# adapter.net
KiCad netlist of a schematic drawn in EAGLE
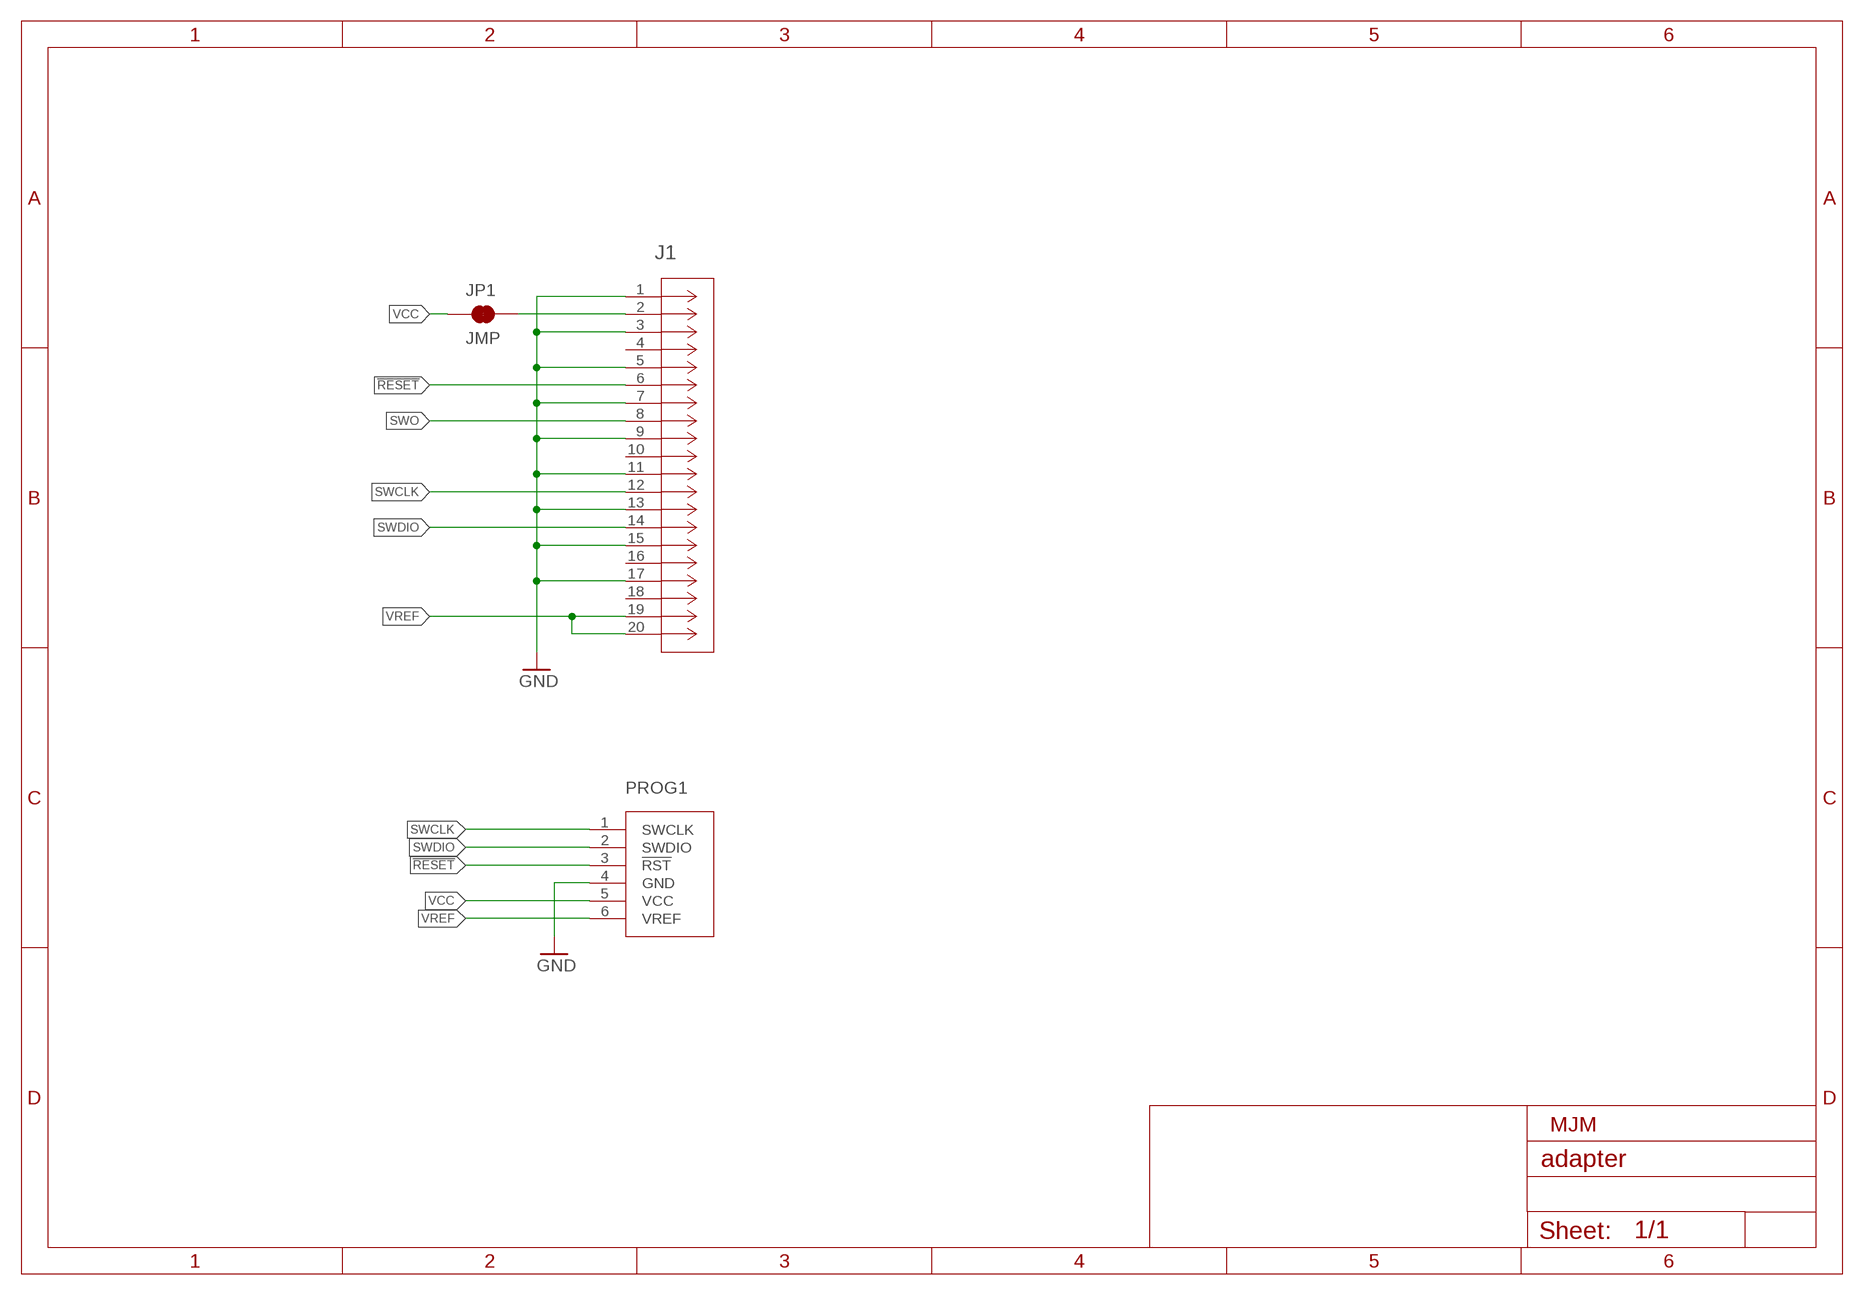
[diagram p0: schematic, sheet 1]

(export (version "E")
  (design (tool "Eeschema 10.0.6"))
  (components
    (comp (ref "J1")
      (value "SFH11-PBPC-D10-ST-BK")
      (footprint "eagle-import:CONN_SFH11-PBPC-D10-ST-BK_SUL")
      (fields (field (name "COPYRIGHT") "Copyright (C) 2018 Accelerated Designs. All rights reserved"))
      (libsource (lib "eagle-import") (part "SFH11-PBPC-D10-ST-BK"))
    )
    (comp (ref "JP1")
      (value "JMP")
      (footprint "eagle-import:SMT-JUMPER_2_NC_TRACE_SILK")
      (libsource (lib "eagle-import") (part "JUMPER-SMT_2_NC_TRACE_SILK"))
    )
    (comp (ref "PROG1")
      (value "0532610671_OP")
      (footprint "eagle-import:0532610671")
      (libsource (lib "eagle-import") (part "0532610671_OP"))
    )
  )
  (nets
    (net (code "1") (name "/~{RESET}") (class "Default")
      (node (ref "J1") (pin "6") (pinfunction "6_6") (pintype "passive"))
      (node (ref "PROG1") (pin "3") (pinfunction "~{RST}_3") (pintype "bidirectional"))
    )
    (net (code "2") (name "GND") (class "Default")
      (node (ref "J1") (pin "1") (pinfunction "1_1") (pintype "passive"))
      (node (ref "J1") (pin "11") (pinfunction "11_11") (pintype "passive"))
      (node (ref "J1") (pin "13") (pinfunction "13_13") (pintype "passive"))
      (node (ref "J1") (pin "15") (pinfunction "15_15") (pintype "passive"))
      (node (ref "J1") (pin "17") (pinfunction "17_17") (pintype "passive"))
      (node (ref "J1") (pin "3") (pinfunction "3_3") (pintype "passive"))
      (node (ref "J1") (pin "5") (pinfunction "5_5") (pintype "passive"))
      (node (ref "J1") (pin "7") (pinfunction "7_7") (pintype "passive"))
      (node (ref "J1") (pin "9") (pinfunction "9_9") (pintype "passive"))
      (node (ref "PROG1") (pin "4") (pinfunction "GND_4") (pintype "bidirectional"))
    )
    (net (code "3") (name "Net-(J1-Pad2)") (class "Default")
      (node (ref "J1") (pin "2") (pinfunction "2_2") (pintype "passive"))
      (node (ref "JP1") (pin "2") (pinfunction "2_2") (pintype "passive"))
    )
    (net (code "4") (name "SWCLK") (class "Default")
      (node (ref "J1") (pin "12") (pinfunction "12_12") (pintype "passive"))
      (node (ref "PROG1") (pin "1") (pinfunction "SWCLK_1") (pintype "bidirectional"))
    )
    (net (code "5") (name "SWDIO") (class "Default")
      (node (ref "J1") (pin "14") (pinfunction "14_14") (pintype "passive"))
      (node (ref "PROG1") (pin "2") (pinfunction "SWDIO_2") (pintype "bidirectional"))
    )
    (net (code "6") (name "SWO") (class "Default")
      (node (ref "J1") (pin "8") (pinfunction "8_8") (pintype "passive"))
    )
    (net (code "7") (name "VCC") (class "Default")
      (node (ref "JP1") (pin "1") (pinfunction "1_1") (pintype "passive"))
      (node (ref "PROG1") (pin "5") (pinfunction "VCC_5") (pintype "bidirectional"))
    )
    (net (code "8") (name "VREF") (class "Default")
      (node (ref "J1") (pin "19") (pinfunction "19_19") (pintype "passive"))
      (node (ref "J1") (pin "20") (pinfunction "20_20") (pintype "passive"))
      (node (ref "PROG1") (pin "6") (pinfunction "VREF_6") (pintype "bidirectional"))
    )
    (net (code "9") (name "unconnected-(J1-Pad4)") (class "Default")
      (node (ref "J1") (pin "4") (pinfunction "4_4") (pintype "passive"))
    )
    (net (code "10") (name "unconnected-(J1-Pad10)") (class "Default")
      (node (ref "J1") (pin "10") (pinfunction "10_10") (pintype "passive"))
    )
    (net (code "11") (name "unconnected-(J1-Pad16)") (class "Default")
      (node (ref "J1") (pin "16") (pinfunction "16_16") (pintype "passive"))
    )
    (net (code "12") (name "unconnected-(J1-Pad18)") (class "Default")
      (node (ref "J1") (pin "18") (pinfunction "18_18") (pintype "passive"))
    )
  )
)
